# tx-slim-2_4g.net
KiCad netlist of a schematic drawn in EAGLE
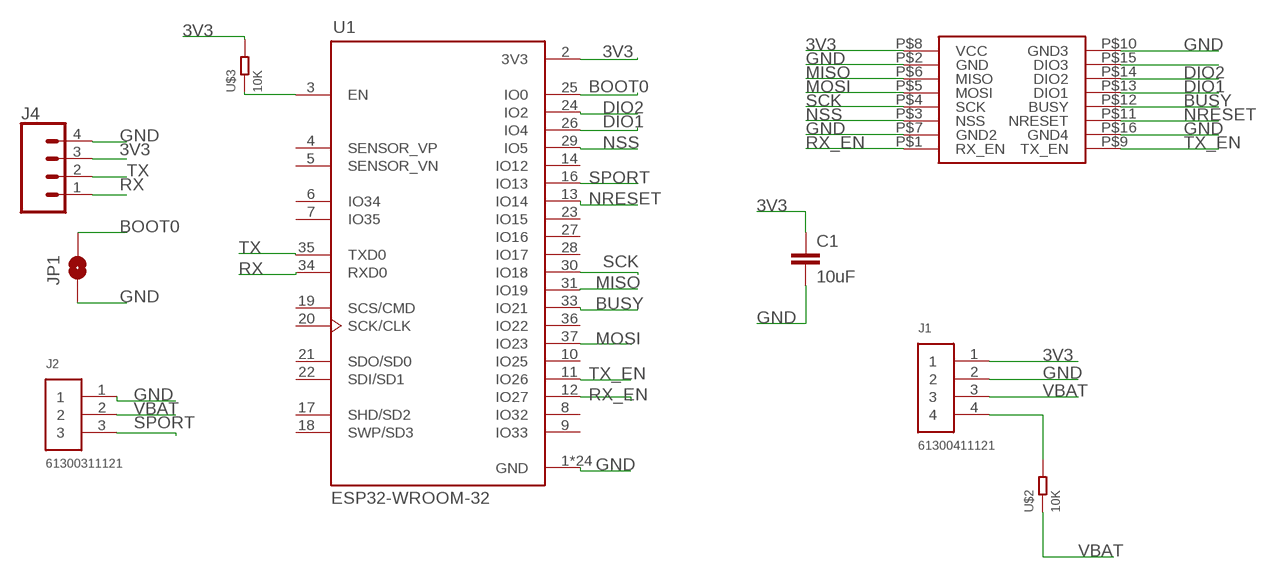
[diagram p0: schematic, sheet 1]

(export (version "E")
  (design (tool "Eeschema 10.0.6"))
  (components
    (comp (ref "C1")
      (value "10uF")
      (footprint "eagle-import:1210")
      (libsource (lib "eagle-import") (part "10UF-1210-50V-20%"))
    )
    (comp (ref "J1")
      (value "61300411121")
      (footprint "eagle-import:61300411121")
      (fields
        (field (name "DIGI_KEY_PART_NUMBER") "732-5317-ND")
        (field (name "MANUFACTURER") "Wurth Electronics Inc.")
        (field (name "CREATED_BY") "PCBLayout.com")
      )
      (libsource (lib "eagle-import") (part "61300411121"))
    )
    (comp (ref "J2")
      (value "61300311121")
      (footprint "eagle-import:61300311121")
      (fields
        (field (name "DIGI_KEY_PART_NUMBER") "732-5316-ND")
        (field (name "MANUFACTURER") "Wurth Electronics Inc.")
        (field (name "CREATED_BY") "PCBLayout.com")
      )
      (libsource (lib "eagle-import") (part "61300311121"))
    )
    (comp (ref "J4")
      (value "CONN_04SMD_RA_FEMALE")
      (footprint "eagle-import:1X04_SMD_RA_FEMALE")
      (libsource (lib "eagle-import") (part "CONN_04SMD_RA_FEMALE"))
    )
    (comp (ref "JP1")
      (value "JUMPER-SMT_2_NO_NO-SILK")
      (footprint "eagle-import:SMT-JUMPER_2_NO_NO-SILK")
      (libsource (lib "eagle-import") (part "JUMPER-SMT_2_NO_NO-SILK"))
    )
    (comp (ref "U$1")
      (value "E28")
      (footprint "eagle-import:E28")
      (libsource (lib "eagle-import") (part "E28"))
    )
    (comp (ref "U$2")
      (value "10K")
      (footprint "eagle-import:R0805")
      (fields (field (name "MPN") "RC0805FR-0710KL"))
      (libsource (lib "eagle-import") (part "SMD-RES-10K-1%-1/8W(0805)"))
    )
    (comp (ref "U$3")
      (value "10K")
      (footprint "eagle-import:R0805")
      (fields (field (name "MPN") "RC0805FR-0710KL"))
      (libsource (lib "eagle-import") (part "SMD-RES-10K-1%-1/8W(0805)"))
    )
    (comp (ref "U1")
      (value "ESP32-WROOM-32")
      (footprint "eagle-import:MODULE_ESP32-WROOM-32")
      (fields (field (name "MF") "Espressif Systems"))
      (libsource (lib "eagle-import") (part "ESP32-WROOM-32"))
    )
  )
  (nets
    (net (code "1") (name "/3V3") (class "Default")
      (node (ref "C1") (pin "1") (pinfunction "1_1") (pintype "passive"))
      (node (ref "J1") (pin "1") (pinfunction "1_1") (pintype "passive"))
      (node (ref "J4") (pin "3") (pinfunction "3_3") (pintype "passive"))
      (node (ref "U$1") (pin "P$8") (pinfunction "VCC_P$8") (pintype "bidirectional"))
      (node (ref "U$3") (pin "2") (pinfunction "2_2") (pintype "passive"))
      (node (ref "U1") (pin "2") (pinfunction "3V3_2") (pintype "power_in"))
    )
    (net (code "2") (name "/BOOT0") (class "Default")
      (node (ref "JP1") (pin "2") (pinfunction "2_2") (pintype "passive"))
      (node (ref "U1") (pin "25") (pinfunction "IO0_25") (pintype "bidirectional"))
    )
    (net (code "3") (name "/BUSY") (class "Default")
      (node (ref "U$1") (pin "P$12") (pinfunction "BUSY_P$12") (pintype "bidirectional"))
      (node (ref "U1") (pin "33") (pinfunction "IO21_33") (pintype "bidirectional"))
    )
    (net (code "4") (name "/DIO1") (class "Default")
      (node (ref "U$1") (pin "P$13") (pinfunction "DIO1_P$13") (pintype "bidirectional"))
      (node (ref "U1") (pin "26") (pinfunction "IO4_26") (pintype "bidirectional"))
    )
    (net (code "5") (name "/DIO2") (class "Default")
      (node (ref "U$1") (pin "P$14") (pinfunction "DIO2_P$14") (pintype "bidirectional"))
      (node (ref "U1") (pin "24") (pinfunction "IO2_24") (pintype "bidirectional"))
    )
    (net (code "6") (name "/GND") (class "Default")
      (node (ref "C1") (pin "2") (pinfunction "2_2") (pintype "passive"))
      (node (ref "J1") (pin "2") (pinfunction "2_2") (pintype "passive"))
      (node (ref "J2") (pin "1") (pinfunction "1_1") (pintype "passive"))
      (node (ref "J4") (pin "4") (pinfunction "4_4") (pintype "passive"))
      (node (ref "JP1") (pin "1") (pinfunction "1_1") (pintype "passive"))
      (node (ref "U$1") (pin "P$10") (pinfunction "GND3_P$10") (pintype "bidirectional"))
      (node (ref "U$1") (pin "P$16") (pinfunction "GND4_P$16") (pintype "bidirectional"))
      (node (ref "U$1") (pin "P$2") (pinfunction "GND_P$2") (pintype "bidirectional"))
      (node (ref "U$1") (pin "P$7") (pinfunction "GND2_P$7") (pintype "bidirectional"))
      (node (ref "U1") (pin "1") (pinfunction "GND_1") (pintype "power_in"))
      (node (ref "U1") (pin "15") (pinfunction "GND_15") (pintype "power_in"))
      (node (ref "U1") (pin "38") (pinfunction "GND_38") (pintype "power_in"))
      (node (ref "U1") (pin "39_1") (pinfunction "GND_39_1") (pintype "power_in"))
      (node (ref "U1") (pin "39_10") (pinfunction "GND_39_10") (pintype "power_in"))
      (node (ref "U1") (pin "39_11") (pinfunction "GND_39_11") (pintype "power_in"))
      (node (ref "U1") (pin "39_12") (pinfunction "GND_39_12") (pintype "power_in"))
      (node (ref "U1") (pin "39_13") (pinfunction "GND_39_13") (pintype "power_in"))
      (node (ref "U1") (pin "39_14") (pinfunction "GND_39_14") (pintype "power_in"))
      (node (ref "U1") (pin "39_15") (pinfunction "GND_39_15") (pintype "power_in"))
      (node (ref "U1") (pin "39_16") (pinfunction "GND_39_16") (pintype "power_in"))
      (node (ref "U1") (pin "39_17") (pinfunction "GND_39_17") (pintype "power_in"))
      (node (ref "U1") (pin "39_18") (pinfunction "GND_39_18") (pintype "power_in"))
      (node (ref "U1") (pin "39_19") (pinfunction "GND_39_19") (pintype "power_in"))
      (node (ref "U1") (pin "39_2") (pinfunction "GND_39_2") (pintype "power_in"))
      (node (ref "U1") (pin "39_20") (pinfunction "GND_39_20") (pintype "power_in"))
      (node (ref "U1") (pin "39_21") (pinfunction "GND_39_21") (pintype "power_in"))
      (node (ref "U1") (pin "39_3") (pinfunction "GND_39_3") (pintype "power_in"))
      (node (ref "U1") (pin "39_4") (pinfunction "GND_39_4") (pintype "power_in"))
      (node (ref "U1") (pin "39_5") (pinfunction "GND_39_5") (pintype "power_in"))
      (node (ref "U1") (pin "39_6") (pinfunction "GND_39_6") (pintype "power_in"))
      (node (ref "U1") (pin "39_7") (pinfunction "GND_39_7") (pintype "power_in"))
      (node (ref "U1") (pin "39_8") (pinfunction "GND_39_8") (pintype "power_in"))
      (node (ref "U1") (pin "39_9") (pinfunction "GND_39_9") (pintype "power_in"))
    )
    (net (code "7") (name "/MISO") (class "Default")
      (node (ref "U$1") (pin "P$6") (pinfunction "MISO_P$6") (pintype "bidirectional"))
      (node (ref "U1") (pin "31") (pinfunction "IO19_31") (pintype "bidirectional"))
    )
    (net (code "8") (name "/MOSI") (class "Default")
      (node (ref "U$1") (pin "P$5") (pinfunction "MOSI_P$5") (pintype "bidirectional"))
      (node (ref "U1") (pin "37") (pinfunction "IO23_37") (pintype "bidirectional"))
    )
    (net (code "9") (name "/NRESET") (class "Default")
      (node (ref "U$1") (pin "P$11") (pinfunction "NRESET_P$11") (pintype "bidirectional"))
      (node (ref "U1") (pin "13") (pinfunction "IO14_13") (pintype "bidirectional"))
    )
    (net (code "10") (name "/NSS") (class "Default")
      (node (ref "U$1") (pin "P$3") (pinfunction "NSS_P$3") (pintype "bidirectional"))
      (node (ref "U1") (pin "29") (pinfunction "IO5_29") (pintype "bidirectional"))
    )
    (net (code "11") (name "/RX") (class "Default")
      (node (ref "J4") (pin "1") (pinfunction "1_1") (pintype "passive"))
      (node (ref "U1") (pin "34") (pinfunction "RXD0_34") (pintype "bidirectional"))
    )
    (net (code "12") (name "/RX_EN") (class "Default")
      (node (ref "U$1") (pin "P$1") (pinfunction "RX_EN_P$1") (pintype "bidirectional"))
      (node (ref "U1") (pin "12") (pinfunction "IO27_12") (pintype "bidirectional"))
    )
    (net (code "13") (name "/SCK") (class "Default")
      (node (ref "U$1") (pin "P$4") (pinfunction "SCK_P$4") (pintype "bidirectional"))
      (node (ref "U1") (pin "30") (pinfunction "IO18_30") (pintype "bidirectional"))
    )
    (net (code "14") (name "/SPORT") (class "Default")
      (node (ref "J2") (pin "3") (pinfunction "3_3") (pintype "passive"))
      (node (ref "U1") (pin "16") (pinfunction "IO13_16") (pintype "bidirectional"))
    )
    (net (code "15") (name "/TX") (class "Default")
      (node (ref "J4") (pin "2") (pinfunction "2_2") (pintype "passive"))
      (node (ref "U1") (pin "35") (pinfunction "TXD0_35") (pintype "bidirectional"))
    )
    (net (code "16") (name "/TX_EN") (class "Default")
      (node (ref "U$1") (pin "P$9") (pinfunction "TX_EN_P$9") (pintype "bidirectional"))
      (node (ref "U1") (pin "11") (pinfunction "IO26_11") (pintype "bidirectional"))
    )
    (net (code "17") (name "/VBAT") (class "Default")
      (node (ref "J1") (pin "3") (pinfunction "3_3") (pintype "passive"))
      (node (ref "J2") (pin "2") (pinfunction "2_2") (pintype "passive"))
      (node (ref "U$2") (pin "1") (pinfunction "1_1") (pintype "passive"))
    )
    (net (code "18") (name "Net-(J1-Pad4)") (class "Default")
      (node (ref "J1") (pin "4") (pinfunction "4_4") (pintype "passive"))
      (node (ref "U$2") (pin "2") (pinfunction "2_2") (pintype "passive"))
    )
    (net (code "19") (name "Net-(U1-EN)") (class "Default")
      (node (ref "U$3") (pin "1") (pinfunction "1_1") (pintype "passive"))
      (node (ref "U1") (pin "3") (pinfunction "EN_3") (pintype "input"))
    )
    (net (code "20") (name "unconnected-(U$1-DIO3-PadP$15)") (class "Default")
      (node (ref "U$1") (pin "P$15") (pinfunction "DIO3_P$15") (pintype "bidirectional"))
    )
    (net (code "21") (name "unconnected-(U1-IO12-Pad14)") (class "Default")
      (node (ref "U1") (pin "14") (pinfunction "IO12_14") (pintype "bidirectional"))
    )
    (net (code "22") (name "unconnected-(U1-IO15-Pad23)") (class "Default")
      (node (ref "U1") (pin "23") (pinfunction "IO15_23") (pintype "bidirectional"))
    )
    (net (code "23") (name "unconnected-(U1-IO16-Pad27)") (class "Default")
      (node (ref "U1") (pin "27") (pinfunction "IO16_27") (pintype "bidirectional"))
    )
    (net (code "24") (name "unconnected-(U1-IO17-Pad28)") (class "Default")
      (node (ref "U1") (pin "28") (pinfunction "IO17_28") (pintype "bidirectional"))
    )
    (net (code "25") (name "unconnected-(U1-IO22-Pad36)") (class "Default")
      (node (ref "U1") (pin "36") (pinfunction "IO22_36") (pintype "bidirectional"))
    )
    (net (code "26") (name "unconnected-(U1-IO25-Pad10)") (class "Default")
      (node (ref "U1") (pin "10") (pinfunction "IO25_10") (pintype "bidirectional"))
    )
    (net (code "27") (name "unconnected-(U1-IO32-Pad8)") (class "Default")
      (node (ref "U1") (pin "8") (pinfunction "IO32_8") (pintype "bidirectional"))
    )
    (net (code "28") (name "unconnected-(U1-IO33-Pad9)") (class "Default")
      (node (ref "U1") (pin "9") (pinfunction "IO33_9") (pintype "bidirectional"))
    )
    (net (code "29") (name "unconnected-(U1-IO34-Pad6)") (class "Default")
      (node (ref "U1") (pin "6") (pinfunction "IO34_6") (pintype "input"))
    )
    (net (code "30") (name "unconnected-(U1-IO35-Pad7)") (class "Default")
      (node (ref "U1") (pin "7") (pinfunction "IO35_7") (pintype "input"))
    )
    (net (code "31") (name "unconnected-(U1-SCK{slash}CLK-Pad20)") (class "Default")
      (node (ref "U1") (pin "20") (pinfunction "SCK/CLK_20") (pintype "bidirectional"))
    )
    (net (code "32") (name "unconnected-(U1-SCS{slash}CMD-Pad19)") (class "Default")
      (node (ref "U1") (pin "19") (pinfunction "SCS/CMD_19") (pintype "bidirectional"))
    )
    (net (code "33") (name "unconnected-(U1-SDI{slash}SD1-Pad22)") (class "Default")
      (node (ref "U1") (pin "22") (pinfunction "SDI/SD1_22") (pintype "bidirectional"))
    )
    (net (code "34") (name "unconnected-(U1-SDO{slash}SD0-Pad21)") (class "Default")
      (node (ref "U1") (pin "21") (pinfunction "SDO/SD0_21") (pintype "bidirectional"))
    )
    (net (code "35") (name "unconnected-(U1-SENSOR_VN-Pad5)") (class "Default")
      (node (ref "U1") (pin "5") (pinfunction "SENSOR_VN_5") (pintype "input"))
    )
    (net (code "36") (name "unconnected-(U1-SENSOR_VP-Pad4)") (class "Default")
      (node (ref "U1") (pin "4") (pinfunction "SENSOR_VP_4") (pintype "input"))
    )
    (net (code "37") (name "unconnected-(U1-SHD{slash}SD2-Pad17)") (class "Default")
      (node (ref "U1") (pin "17") (pinfunction "SHD/SD2_17") (pintype "bidirectional"))
    )
    (net (code "38") (name "unconnected-(U1-SWP{slash}SD3-Pad18)") (class "Default")
      (node (ref "U1") (pin "18") (pinfunction "SWP/SD3_18") (pintype "bidirectional"))
    )
  )
)
